# ArmazConnect_-_Rev_B2.net
KiCad netlist of a schematic drawn in EAGLE
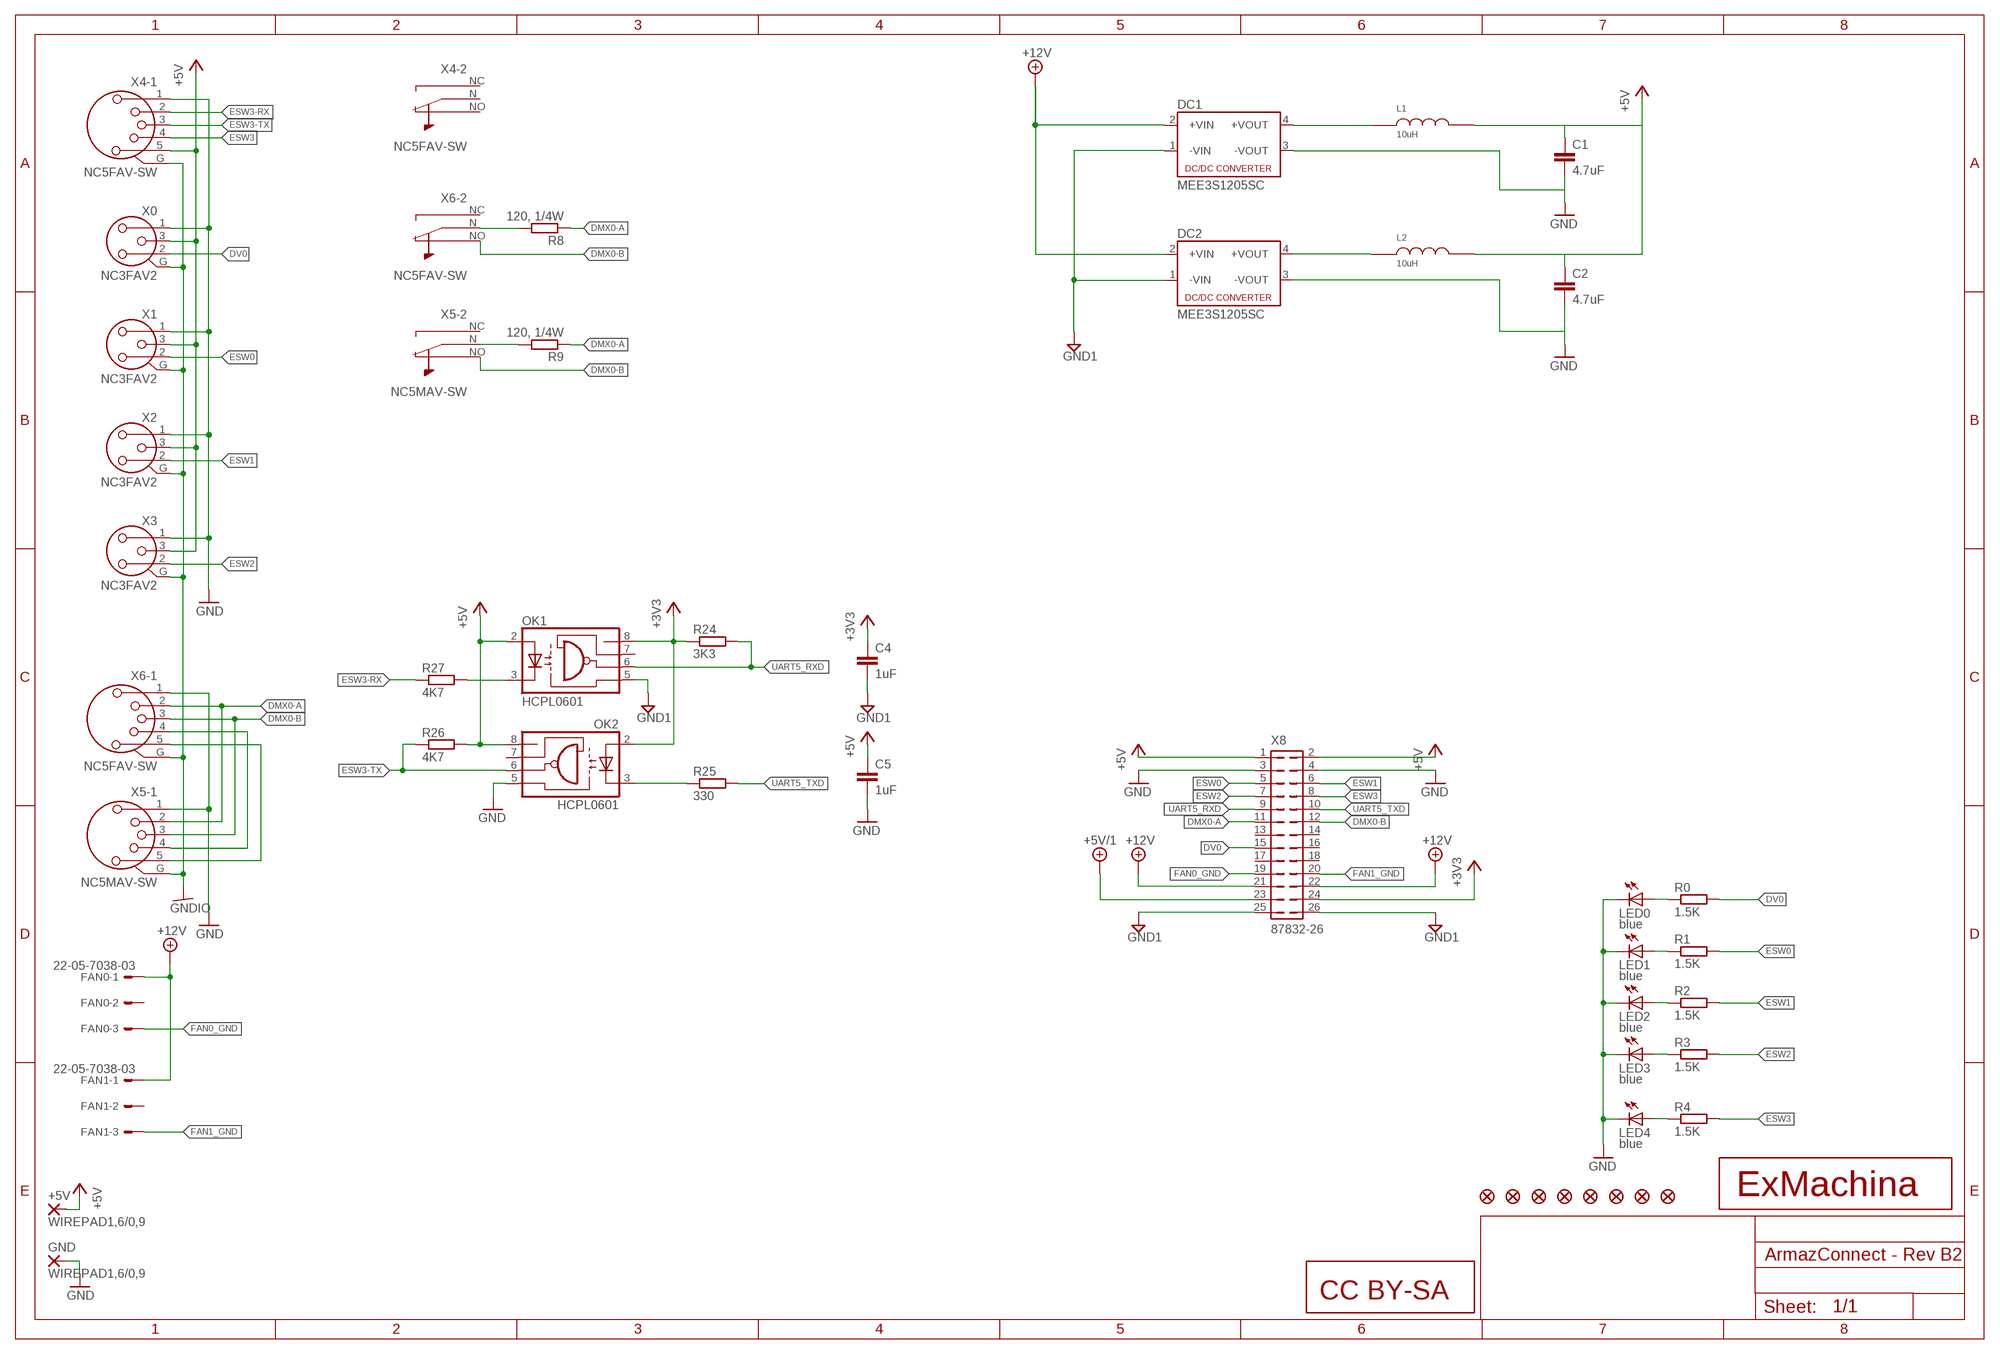
[diagram p0: schematic, sheet 1]

(export (version "E")
  (design (tool "Eeschema 10.0.6"))
  (components
    (comp (ref "+5V")
      (value "WIREPAD1,6/0,9")
      (footprint "eagle-import:1,6_0,9")
      (libsource (lib "eagle-import") (part "WIREPAD1,6/0,9"))
    )
    (comp (ref "C1")
      (value "4.7uF")
      (footprint "eagle-import:C0603")
      (fields (field (name "MF") "MULTICOMP") (field (name "MPN") "MC0603X475K6R3CT"))
      (libsource (lib "eagle-import") (part "C-EUC0603"))
    )
    (comp (ref "C2")
      (value "4.7uF")
      (footprint "eagle-import:C0603")
      (fields (field (name "MF") "MULTICOMP") (field (name "MPN") "MC0603X475K6R3CT"))
      (libsource (lib "eagle-import") (part "C-EUC0603"))
    )
    (comp (ref "C4")
      (value "1uF")
      (footprint "eagle-import:C0805")
      (fields (field (name "MF") "MULTICOMP") (field (name "MPN") "MC0805F105Z500CT"))
      (libsource (lib "eagle-import") (part "C-EUC0805"))
    )
    (comp (ref "C5")
      (value "1uF")
      (footprint "eagle-import:C0805")
      (fields (field (name "MF") "MULTICOMP") (field (name "MPN") "MC0805F105Z500CT"))
      (libsource (lib "eagle-import") (part "C-EUC0805"))
    )
    (comp (ref "DC1")
      (value "MEE3S1205SC")
      (footprint "eagle-import:MEE3")
      (fields (field (name "MF") "MURATA POWER SOLUTIONS"))
      (libsource (lib "eagle-import") (part "MEE3S1205SC"))
    )
    (comp (ref "DC2")
      (value "MEE3S1205SC")
      (footprint "eagle-import:MEE3")
      (fields (field (name "MF") "MURATA POWER SOLUTIONS"))
      (libsource (lib "eagle-import") (part "MEE3S1205SC"))
    )
    (comp (ref "FAN0")
      (value "22-05-7038-03")
      (footprint "eagle-import:7395-03")
      (fields
        (field (name "MF") "MOLEX")
        (field (name "MPN") "22-05-7038")
        (field (name "OC_FARNELL") "9731610")
      )
      (libsource (lib "eagle-import") (part "22-?-0305-7038"))
    )
    (comp (ref "FAN1")
      (value "22-05-7038-03")
      (footprint "eagle-import:7395-03")
      (fields
        (field (name "MF") "MOLEX")
        (field (name "MPN") "22-05-7038")
        (field (name "OC_FARNELL") "9731610")
      )
      (libsource (lib "eagle-import") (part "22-?-0305-7038"))
    )
    (comp (ref "FI1")
      (value "FIDUCIAL1X2")
      (footprint "eagle-import:FIDUCIAL-1X2")
      (libsource (lib "eagle-import") (part "FIDUCIAL1X2"))
    )
    (comp (ref "FI2")
      (value "FIDUCIAL1X2")
      (footprint "eagle-import:FIDUCIAL-1X2")
      (libsource (lib "eagle-import") (part "FIDUCIAL1X2"))
    )
    (comp (ref "FI3")
      (value "FIDUCIAL1X2")
      (footprint "eagle-import:FIDUCIAL-1X2")
      (libsource (lib "eagle-import") (part "FIDUCIAL1X2"))
    )
    (comp (ref "FI4")
      (value "FIDUCIAL1X2")
      (footprint "eagle-import:FIDUCIAL-1X2")
      (libsource (lib "eagle-import") (part "FIDUCIAL1X2"))
    )
    (comp (ref "FI5")
      (value "FIDUCIAL1X2")
      (footprint "eagle-import:FIDUCIAL-1X2")
      (libsource (lib "eagle-import") (part "FIDUCIAL1X2"))
    )
    (comp (ref "FI6")
      (value "FIDUCIAL1X2")
      (footprint "eagle-import:FIDUCIAL-1X2")
      (libsource (lib "eagle-import") (part "FIDUCIAL1X2"))
    )
    (comp (ref "FI7")
      (value "FIDUCIAL1X2")
      (footprint "eagle-import:FIDUCIAL-1X2")
      (libsource (lib "eagle-import") (part "FIDUCIAL1X2"))
    )
    (comp (ref "FI8")
      (value "FIDUCIAL1X2")
      (footprint "eagle-import:FIDUCIAL-1X2")
      (libsource (lib "eagle-import") (part "FIDUCIAL1X2"))
    )
    (comp (ref "GND")
      (value "WIREPAD1,6/0,9")
      (footprint "eagle-import:1,6_0,9")
      (libsource (lib "eagle-import") (part "WIREPAD1,6/0,9"))
    )
    (comp (ref "L1")
      (value "10uH")
      (footprint "eagle-import:8200")
      (fields (field (name "MF") "WURTH ELEKTRONIK") (field (name "MPN") "744045100"))
      (libsource (lib "eagle-import") (part "84103C"))
    )
    (comp (ref "L2")
      (value "10uH")
      (footprint "eagle-import:8200")
      (fields (field (name "MF") "WURTH ELEKTRONIK") (field (name "MPN") "744045100"))
      (libsource (lib "eagle-import") (part "84103C"))
    )
    (comp (ref "LED0")
      (value "blue")
      (footprint "eagle-import:CHIP-LED0603")
      (fields (field (name "MF") "MULTICOMP") (field (name "MPN") "OVS-0603"))
      (libsource (lib "eagle-import") (part "LEDCHIP-LED0603"))
    )
    (comp (ref "LED1")
      (value "blue")
      (footprint "eagle-import:CHIP-LED0603")
      (fields (field (name "MF") "MULTICOMP") (field (name "MPN") "OVS-0603"))
      (libsource (lib "eagle-import") (part "LEDCHIP-LED0603"))
    )
    (comp (ref "LED2")
      (value "blue")
      (footprint "eagle-import:CHIP-LED0603")
      (fields (field (name "MF") "MULTICOMP") (field (name "MPN") "OVS-0603"))
      (libsource (lib "eagle-import") (part "LEDCHIP-LED0603"))
    )
    (comp (ref "LED3")
      (value "blue")
      (footprint "eagle-import:CHIP-LED0603")
      (fields (field (name "MF") "MULTICOMP") (field (name "MPN") "OVS-0603"))
      (libsource (lib "eagle-import") (part "LEDCHIP-LED0603"))
    )
    (comp (ref "LED4")
      (value "blue")
      (footprint "eagle-import:CHIP-LED0603")
      (fields (field (name "MF") "MULTICOMP") (field (name "MPN") "OVS-0603"))
      (libsource (lib "eagle-import") (part "LEDCHIP-LED0603"))
    )
    (comp (ref "OK1")
      (value "HCPL0601")
      (footprint "eagle-import:SOIC08")
      (fields
        (field (name "MF") "AGILENT TECHNOLOGIES")
        (field (name "MPN") "HCPL-0601-000E")
        (field (name "MF_1") "AVAGO TECHNOLOGIES")
      )
      (libsource (lib "eagle-import") (part "HCPL0601"))
    )
    (comp (ref "OK2")
      (value "HCPL0601")
      (footprint "eagle-import:SOIC08")
      (fields
        (field (name "MF") "AGILENT TECHNOLOGIES")
        (field (name "MPN") "HCPL-0601-000E")
        (field (name "MF_1") "AVAGO TECHNOLOGIES")
      )
      (libsource (lib "eagle-import") (part "HCPL0601"))
    )
    (comp (ref "R0")
      (value "1.5K")
      (footprint "eagle-import:R0603")
      (fields (field (name "MF") "MULTICOMP") (field (name "MPN") "MCMR06X1501FTL"))
      (libsource (lib "eagle-import") (part "R-EU_R0603"))
    )
    (comp (ref "R1")
      (value "1.5K")
      (footprint "eagle-import:R0603")
      (fields (field (name "MF") "MULTICOMP") (field (name "MPN") "MCMR06X1501FTL"))
      (libsource (lib "eagle-import") (part "R-EU_R0603"))
    )
    (comp (ref "R2")
      (value "1.5K")
      (footprint "eagle-import:R0603")
      (fields (field (name "MF") "MULTICOMP") (field (name "MPN") "MCMR06X1501FTL"))
      (libsource (lib "eagle-import") (part "R-EU_R0603"))
    )
    (comp (ref "R3")
      (value "1.5K")
      (footprint "eagle-import:R0603")
      (fields (field (name "MF") "MULTICOMP") (field (name "MPN") "MCMR06X1501FTL"))
      (libsource (lib "eagle-import") (part "R-EU_R0603"))
    )
    (comp (ref "R4")
      (value "1.5K")
      (footprint "eagle-import:R0603")
      (fields (field (name "MF") "MULTICOMP") (field (name "MPN") "MCMR06X1501FTL"))
      (libsource (lib "eagle-import") (part "R-EU_R0603"))
    )
    (comp (ref "R8")
      (value "120, 1/4W")
      (footprint "eagle-import:R0603")
      (fields (field (name "MF") "MULTICOMP") (field (name "MPN") "MCMR06X1200FTL"))
      (libsource (lib "eagle-import") (part "R-EU_R0603"))
    )
    (comp (ref "R9")
      (value "120, 1/4W")
      (footprint "eagle-import:R0603")
      (fields (field (name "MF") "MULTICOMP") (field (name "MPN") "MCMR06X1200FTL"))
      (libsource (lib "eagle-import") (part "R-EU_R0603"))
    )
    (comp (ref "R24")
      (value "3K3")
      (footprint "eagle-import:R0402")
      (fields (field (name "MF") "MULTICOMP") (field (name "MPN") "MCMR04X3301FTL"))
      (libsource (lib "eagle-import") (part "R-EU_R0402"))
    )
    (comp (ref "R25")
      (value "330")
      (footprint "eagle-import:R0603")
      (fields (field (name "MF") "MULTICOMP") (field (name "MPN") "MCMR06X3300FTL"))
      (libsource (lib "eagle-import") (part "R-EU_R0603"))
    )
    (comp (ref "R26")
      (value "4K7")
      (footprint "eagle-import:R0603")
      (fields (field (name "MF") "MULTICOMP") (field (name "MPN") "MCMR06X4701FTL"))
      (libsource (lib "eagle-import") (part "R-EU_R0603"))
    )
    (comp (ref "R27")
      (value "4K7")
      (footprint "eagle-import:R0603")
      (fields (field (name "MF") "MULTICOMP") (field (name "MPN") "MCMR06X4701FTL"))
      (libsource (lib "eagle-import") (part "R-EU_R0603"))
    )
    (comp (ref "U$1")
      (value "EXMACHINA-LOGO-NAME")
      (footprint "eagle-import:EXM-LOGO-BASELINE")
      (libsource (lib "eagle-import") (part "EXMACHINA-LOGO-NAME"))
    )
    (comp (ref "U$2")
      (value "CC-BY-SA")
      (footprint "eagle-import:CC-BY-SA")
      (libsource (lib "eagle-import") (part "CC-BY-SA"))
    )
    (comp (ref "X0")
      (value "NC3FAV2")
      (footprint "eagle-import:NC3FAV2")
      (fields
        (field (name "MF") "NEUTRIK")
        (field (name "MPN") "NC3FAAV2")
        (field (name "OC_FARNELL") "1310038")
      )
      (libsource (lib "eagle-import") (part "NC3FAV2"))
    )
    (comp (ref "X1")
      (value "NC3FAV2")
      (footprint "eagle-import:NC3FAV2")
      (fields
        (field (name "MF") "NEUTRIK")
        (field (name "MPN") "NC3FAAV2")
        (field (name "OC_FARNELL") "1310038")
      )
      (libsource (lib "eagle-import") (part "NC3FAV2"))
    )
    (comp (ref "X2")
      (value "NC3FAV2")
      (footprint "eagle-import:NC3FAV2")
      (fields
        (field (name "MF") "NEUTRIK")
        (field (name "MPN") "NC3FAAV2")
        (field (name "OC_FARNELL") "1310038")
      )
      (libsource (lib "eagle-import") (part "NC3FAV2"))
    )
    (comp (ref "X3")
      (value "NC3FAV2")
      (footprint "eagle-import:NC3FAV2")
      (fields
        (field (name "MF") "NEUTRIK")
        (field (name "MPN") "NC3FAAV2")
        (field (name "OC_FARNELL") "1310038")
      )
      (libsource (lib "eagle-import") (part "NC3FAV2"))
    )
    (comp (ref "X4")
      (value "NC5FAV-SW")
      (footprint "eagle-import:NC5FAV-SW")
      (fields (field (name "MF") "NEUTRIK") (field (name "OC_FARNELL") "1310093"))
      (libsource (lib "eagle-import") (part "NC5?-SWFAV"))
    )
    (comp (ref "X5")
      (value "NC5MAV-SW")
      (footprint "eagle-import:NC5MAV-SW")
      (fields
        (field (name "MF") "NETRIK")
        (field (name "MF_1") "NEUTRIK")
        (field (name "OC_FARNELL") "1310098")
      )
      (libsource (lib "eagle-import") (part "NC5?-SWMAV"))
    )
    (comp (ref "X6")
      (value "NC5FAV-SW")
      (footprint "eagle-import:NC5FAV-SW")
      (fields (field (name "MF") "NEUTRIK") (field (name "OC_FARNELL") "1310093"))
      (libsource (lib "eagle-import") (part "NC5?-SWFAV"))
    )
    (comp (ref "X8")
      (value "87832-26")
      (footprint "eagle-import:87832-26")
      (fields
        (field (name "MF") "MOLEX")
        (field (name "MPN") "87832-2620")
        (field (name "OC_FARNELL") "2313712")
      )
      (libsource (lib "eagle-import") (part "87832-26"))
    )
  )
  (nets
    (net (code "1") (name "+3V3") (class "Default")
      (node (ref "C4") (pin "1") (pinfunction "1_1") (pintype "passive"))
      (node (ref "OK1") (pin "8") (pinfunction "VCC_8") (pintype "passive"))
      (node (ref "OK2") (pin "2") (pinfunction "A_2") (pintype "passive"))
      (node (ref "R24") (pin "1") (pinfunction "1_1") (pintype "passive"))
      (node (ref "X8") (pin "24") (pinfunction "24_24") (pintype "passive"))
    )
    (net (code "2") (name "+5V") (class "Default")
      (node (ref "+5V") (pin "1") (pinfunction "P_1") (pintype "passive"))
      (node (ref "C1") (pin "1") (pinfunction "1_1") (pintype "passive"))
      (node (ref "C2") (pin "1") (pinfunction "1_1") (pintype "passive"))
      (node (ref "C5") (pin "1") (pinfunction "1_1") (pintype "passive"))
      (node (ref "L1") (pin "2") (pinfunction "2_2") (pintype "passive"))
      (node (ref "L2") (pin "2") (pinfunction "2_2") (pintype "passive"))
      (node (ref "OK1") (pin "2") (pinfunction "A_2") (pintype "passive"))
      (node (ref "OK2") (pin "8") (pinfunction "VCC_8") (pintype "passive"))
      (node (ref "R26") (pin "2") (pinfunction "2_2") (pintype "passive"))
      (node (ref "X0") (pin "3") (pinfunction "3_3") (pintype "passive"))
      (node (ref "X1") (pin "3") (pinfunction "3_3") (pintype "passive"))
      (node (ref "X2") (pin "3") (pinfunction "3_3") (pintype "passive"))
      (node (ref "X3") (pin "3") (pinfunction "3_3") (pintype "passive"))
      (node (ref "X4") (pin "5") (pinfunction "5_5") (pintype "passive"))
      (node (ref "X8") (pin "1") (pinfunction "1_1") (pintype "passive"))
      (node (ref "X8") (pin "2") (pinfunction "2_2") (pintype "passive"))
    )
    (net (code "3") (name "+5V{slash}1") (class "Default")
      (node (ref "X8") (pin "23") (pinfunction "23_23") (pintype "passive"))
    )
    (net (code "4") (name "+12V") (class "Default")
      (node (ref "DC1") (pin "2") (pinfunction "+VIN_2") (pintype "passive"))
      (node (ref "DC2") (pin "2") (pinfunction "+VIN_2") (pintype "passive"))
      (node (ref "FAN0") (pin "1") (pinfunction "S_1") (pintype "passive"))
      (node (ref "FAN1") (pin "1") (pinfunction "S_1") (pintype "passive"))
      (node (ref "X8") (pin "21") (pinfunction "21_21") (pintype "passive"))
      (node (ref "X8") (pin "22") (pinfunction "22_22") (pintype "passive"))
    )
    (net (code "5") (name "DMX0-A") (class "Default")
      (node (ref "R8") (pin "1") (pinfunction "1_1") (pintype "passive"))
      (node (ref "R9") (pin "1") (pinfunction "1_1") (pintype "passive"))
      (node (ref "X5") (pin "2") (pinfunction "2_2") (pintype "passive"))
      (node (ref "X6") (pin "2") (pinfunction "2_2") (pintype "passive"))
      (node (ref "X8") (pin "11") (pinfunction "11_11") (pintype "passive"))
    )
    (net (code "6") (name "DMX0-B") (class "Default")
      (node (ref "X5") (pin "3") (pinfunction "3_3") (pintype "passive"))
      (node (ref "X5") (pin "NO") (pinfunction "NO_NO") (pintype "passive"))
      (node (ref "X6") (pin "3") (pinfunction "3_3") (pintype "passive"))
      (node (ref "X6") (pin "NO") (pinfunction "NO_NO") (pintype "passive"))
      (node (ref "X8") (pin "12") (pinfunction "12_12") (pintype "passive"))
    )
    (net (code "7") (name "DV0") (class "Default")
      (node (ref "R0") (pin "2") (pinfunction "2_2") (pintype "passive"))
      (node (ref "X0") (pin "2") (pinfunction "2_2") (pintype "passive"))
      (node (ref "X8") (pin "15") (pinfunction "15_15") (pintype "passive"))
    )
    (net (code "8") (name "ESW0") (class "Default")
      (node (ref "R1") (pin "2") (pinfunction "2_2") (pintype "passive"))
      (node (ref "X1") (pin "2") (pinfunction "2_2") (pintype "passive"))
      (node (ref "X8") (pin "5") (pinfunction "5_5") (pintype "passive"))
    )
    (net (code "9") (name "ESW1") (class "Default")
      (node (ref "R2") (pin "2") (pinfunction "2_2") (pintype "passive"))
      (node (ref "X2") (pin "2") (pinfunction "2_2") (pintype "passive"))
      (node (ref "X8") (pin "6") (pinfunction "6_6") (pintype "passive"))
    )
    (net (code "10") (name "ESW2") (class "Default")
      (node (ref "R3") (pin "2") (pinfunction "2_2") (pintype "passive"))
      (node (ref "X3") (pin "2") (pinfunction "2_2") (pintype "passive"))
      (node (ref "X8") (pin "7") (pinfunction "7_7") (pintype "passive"))
    )
    (net (code "11") (name "ESW3") (class "Default")
      (node (ref "R4") (pin "2") (pinfunction "2_2") (pintype "passive"))
      (node (ref "X4") (pin "4") (pinfunction "4_4") (pintype "passive"))
      (node (ref "X8") (pin "8") (pinfunction "8_8") (pintype "passive"))
    )
    (net (code "12") (name "ESW3-RX") (class "Default")
      (node (ref "R27") (pin "1") (pinfunction "1_1") (pintype "passive"))
      (node (ref "X4") (pin "2") (pinfunction "2_2") (pintype "passive"))
    )
    (net (code "13") (name "ESW3-TX") (class "Default")
      (node (ref "OK2") (pin "6") (pinfunction "VO_6") (pintype "passive"))
      (node (ref "R26") (pin "1") (pinfunction "1_1") (pintype "passive"))
      (node (ref "X4") (pin "3") (pinfunction "3_3") (pintype "passive"))
    )
    (net (code "14") (name "FAN0_GND") (class "Default")
      (node (ref "FAN0") (pin "3") (pinfunction "S_3") (pintype "passive"))
      (node (ref "X8") (pin "19") (pinfunction "19_19") (pintype "passive"))
    )
    (net (code "15") (name "FAN1_GND") (class "Default")
      (node (ref "FAN1") (pin "3") (pinfunction "S_3") (pintype "passive"))
      (node (ref "X8") (pin "20") (pinfunction "20_20") (pintype "passive"))
    )
    (net (code "16") (name "GND") (class "Default")
      (node (ref "C1") (pin "2") (pinfunction "2_2") (pintype "passive"))
      (node (ref "C2") (pin "2") (pinfunction "2_2") (pintype "passive"))
      (node (ref "C5") (pin "2") (pinfunction "2_2") (pintype "passive"))
      (node (ref "DC1") (pin "3") (pinfunction "-VOUT_3") (pintype "passive"))
      (node (ref "DC2") (pin "3") (pinfunction "-VOUT_3") (pintype "passive"))
      (node (ref "GND") (pin "1") (pinfunction "P_1") (pintype "passive"))
      (node (ref "LED0") (pin "C") (pinfunction "C_C") (pintype "passive"))
      (node (ref "LED1") (pin "C") (pinfunction "C_C") (pintype "passive"))
      (node (ref "LED2") (pin "C") (pinfunction "C_C") (pintype "passive"))
      (node (ref "LED3") (pin "C") (pinfunction "C_C") (pintype "passive"))
      (node (ref "LED4") (pin "C") (pinfunction "C_C") (pintype "passive"))
      (node (ref "OK2") (pin "5") (pinfunction "GND_5") (pintype "passive"))
      (node (ref "X0") (pin "1") (pinfunction "1_1") (pintype "passive"))
      (node (ref "X1") (pin "1") (pinfunction "1_1") (pintype "passive"))
      (node (ref "X2") (pin "1") (pinfunction "1_1") (pintype "passive"))
      (node (ref "X3") (pin "1") (pinfunction "1_1") (pintype "passive"))
      (node (ref "X4") (pin "1") (pinfunction "1_1") (pintype "passive"))
      (node (ref "X5") (pin "1") (pinfunction "1_1") (pintype "passive"))
      (node (ref "X6") (pin "1") (pinfunction "1_1") (pintype "passive"))
      (node (ref "X8") (pin "3") (pinfunction "3_3") (pintype "passive"))
      (node (ref "X8") (pin "4") (pinfunction "4_4") (pintype "passive"))
    )
    (net (code "17") (name "GND1") (class "Default")
      (node (ref "C4") (pin "2") (pinfunction "2_2") (pintype "passive"))
      (node (ref "DC1") (pin "1") (pinfunction "-VIN_1") (pintype "passive"))
      (node (ref "DC2") (pin "1") (pinfunction "-VIN_1") (pintype "passive"))
      (node (ref "OK1") (pin "5") (pinfunction "GND_5") (pintype "passive"))
      (node (ref "X8") (pin "25") (pinfunction "25_25") (pintype "passive"))
      (node (ref "X8") (pin "26") (pinfunction "26_26") (pintype "passive"))
    )
    (net (code "18") (name "GNDIO") (class "Default")
      (node (ref "X0") (pin "G") (pinfunction "G_G") (pintype "passive"))
      (node (ref "X1") (pin "G") (pinfunction "G_G") (pintype "passive"))
      (node (ref "X2") (pin "G") (pinfunction "G_G") (pintype "passive"))
      (node (ref "X3") (pin "G") (pinfunction "G_G") (pintype "passive"))
      (node (ref "X4") (pin "G") (pinfunction "G_G") (pintype "passive"))
      (node (ref "X5") (pin "G") (pinfunction "G_G") (pintype "passive"))
      (node (ref "X6") (pin "G") (pinfunction "G_G") (pintype "passive"))
    )
    (net (code "19") (name "Net-(DC1-+VOUT)") (class "Default")
      (node (ref "DC1") (pin "4") (pinfunction "+VOUT_4") (pintype "passive"))
      (node (ref "L1") (pin "1") (pinfunction "1_1") (pintype "passive"))
    )
    (net (code "20") (name "Net-(DC2-+VOUT)") (class "Default")
      (node (ref "DC2") (pin "4") (pinfunction "+VOUT_4") (pintype "passive"))
      (node (ref "L2") (pin "1") (pinfunction "1_1") (pintype "passive"))
    )
    (net (code "21") (name "Net-(LED0-PadA)") (class "Default")
      (node (ref "LED0") (pin "A") (pinfunction "A_A") (pintype "passive"))
      (node (ref "R0") (pin "1") (pinfunction "1_1") (pintype "passive"))
    )
    (net (code "22") (name "Net-(LED1-PadA)") (class "Default")
      (node (ref "LED1") (pin "A") (pinfunction "A_A") (pintype "passive"))
      (node (ref "R1") (pin "1") (pinfunction "1_1") (pintype "passive"))
    )
    (net (code "23") (name "Net-(LED2-PadA)") (class "Default")
      (node (ref "LED2") (pin "A") (pinfunction "A_A") (pintype "passive"))
      (node (ref "R2") (pin "1") (pinfunction "1_1") (pintype "passive"))
    )
    (net (code "24") (name "Net-(LED3-PadA)") (class "Default")
      (node (ref "LED3") (pin "A") (pinfunction "A_A") (pintype "passive"))
      (node (ref "R3") (pin "1") (pinfunction "1_1") (pintype "passive"))
    )
    (net (code "25") (name "Net-(LED4-PadA)") (class "Default")
      (node (ref "LED4") (pin "A") (pinfunction "A_A") (pintype "passive"))
      (node (ref "R4") (pin "1") (pinfunction "1_1") (pintype "passive"))
    )
    (net (code "26") (name "Net-(OK1-C)") (class "Default")
      (node (ref "OK1") (pin "3") (pinfunction "C_3") (pintype "passive"))
      (node (ref "R27") (pin "2") (pinfunction "2_2") (pintype "passive"))
    )
    (net (code "27") (name "Net-(OK2-C)") (class "Default")
      (node (ref "OK2") (pin "3") (pinfunction "C_3") (pintype "passive"))
      (node (ref "R25") (pin "1") (pinfunction "1_1") (pintype "passive"))
    )
    (net (code "28") (name "Net-(R8-Pad2)") (class "Default")
      (node (ref "R8") (pin "2") (pinfunction "2_2") (pintype "passive"))
      (node (ref "X6") (pin "N") (pinfunction "N_N") (pintype "passive"))
    )
    (net (code "29") (name "Net-(R9-Pad2)") (class "Default")
      (node (ref "R9") (pin "2") (pinfunction "2_2") (pintype "passive"))
      (node (ref "X5") (pin "N") (pinfunction "N_N") (pintype "passive"))
    )
    (net (code "30") (name "Net-(X5-Pad4)") (class "Default")
      (node (ref "X5") (pin "4") (pinfunction "4_4") (pintype "passive"))
      (node (ref "X6") (pin "4") (pinfunction "4_4") (pintype "passive"))
    )
    (net (code "31") (name "Net-(X5-Pad5)") (class "Default")
      (node (ref "X5") (pin "5") (pinfunction "5_5") (pintype "passive"))
      (node (ref "X6") (pin "5") (pinfunction "5_5") (pintype "passive"))
    )
    (net (code "32") (name "UART5_RXD") (class "Default")
      (node (ref "OK1") (pin "6") (pinfunction "VO_6") (pintype "passive"))
      (node (ref "R24") (pin "2") (pinfunction "2_2") (pintype "passive"))
      (node (ref "X8") (pin "9") (pinfunction "9_9") (pintype "passive"))
    )
    (net (code "33") (name "UART5_TXD") (class "Default")
      (node (ref "R25") (pin "2") (pinfunction "2_2") (pintype "passive"))
      (node (ref "X8") (pin "10") (pinfunction "10_10") (pintype "passive"))
    )
    (net (code "34") (name "unconnected-(FAN0B-S-Pad2)") (class "Default")
      (node (ref "FAN0") (pin "2") (pinfunction "S_2") (pintype "passive"))
    )
    (net (code "35") (name "unconnected-(FAN1B-S-Pad2)") (class "Default")
      (node (ref "FAN1") (pin "2") (pinfunction "S_2") (pintype "passive"))
    )
    (net (code "36") (name "unconnected-(OK1-VE-Pad7)") (class "Default")
      (node (ref "OK1") (pin "7") (pinfunction "VE_7") (pintype "passive"))
    )
    (net (code "37") (name "unconnected-(OK2-VE-Pad7)") (class "Default")
      (node (ref "OK2") (pin "7") (pinfunction "VE_7") (pintype "passive"))
    )
    (net (code "38") (name "unconnected-(X4-PadN)") (class "Default")
      (node (ref "X4") (pin "N") (pinfunction "N_N") (pintype "passive"))
    )
    (net (code "39") (name "unconnected-(X4-PadNC)") (class "Default")
      (node (ref "X4") (pin "NC") (pinfunction "NC_NC") (pintype "passive"))
    )
    (net (code "40") (name "unconnected-(X4-PadNO)") (class "Default")
      (node (ref "X4") (pin "NO") (pinfunction "NO_NO") (pintype "passive"))
    )
    (net (code "41") (name "unconnected-(X5-PadNC)") (class "Default")
      (node (ref "X5") (pin "NC") (pinfunction "NC_NC") (pintype "passive"))
    )
    (net (code "42") (name "unconnected-(X6-PadNC)") (class "Default")
      (node (ref "X6") (pin "NC") (pinfunction "NC_NC") (pintype "passive"))
    )
    (net (code "43") (name "unconnected-(X8-Pad13)") (class "Default")
      (node (ref "X8") (pin "13") (pinfunction "13_13") (pintype "passive"))
    )
    (net (code "44") (name "unconnected-(X8-Pad14)") (class "Default")
      (node (ref "X8") (pin "14") (pinfunction "14_14") (pintype "passive"))
    )
    (net (code "45") (name "unconnected-(X8-Pad16)") (class "Default")
      (node (ref "X8") (pin "16") (pinfunction "16_16") (pintype "passive"))
    )
    (net (code "46") (name "unconnected-(X8-Pad17)") (class "Default")
      (node (ref "X8") (pin "17") (pinfunction "17_17") (pintype "passive"))
    )
    (net (code "47") (name "unconnected-(X8-Pad18)") (class "Default")
      (node (ref "X8") (pin "18") (pinfunction "18_18") (pintype "passive"))
    )
  )
)
